# BLE-BMS.net
KiCad netlist of a schematic drawn in EAGLE
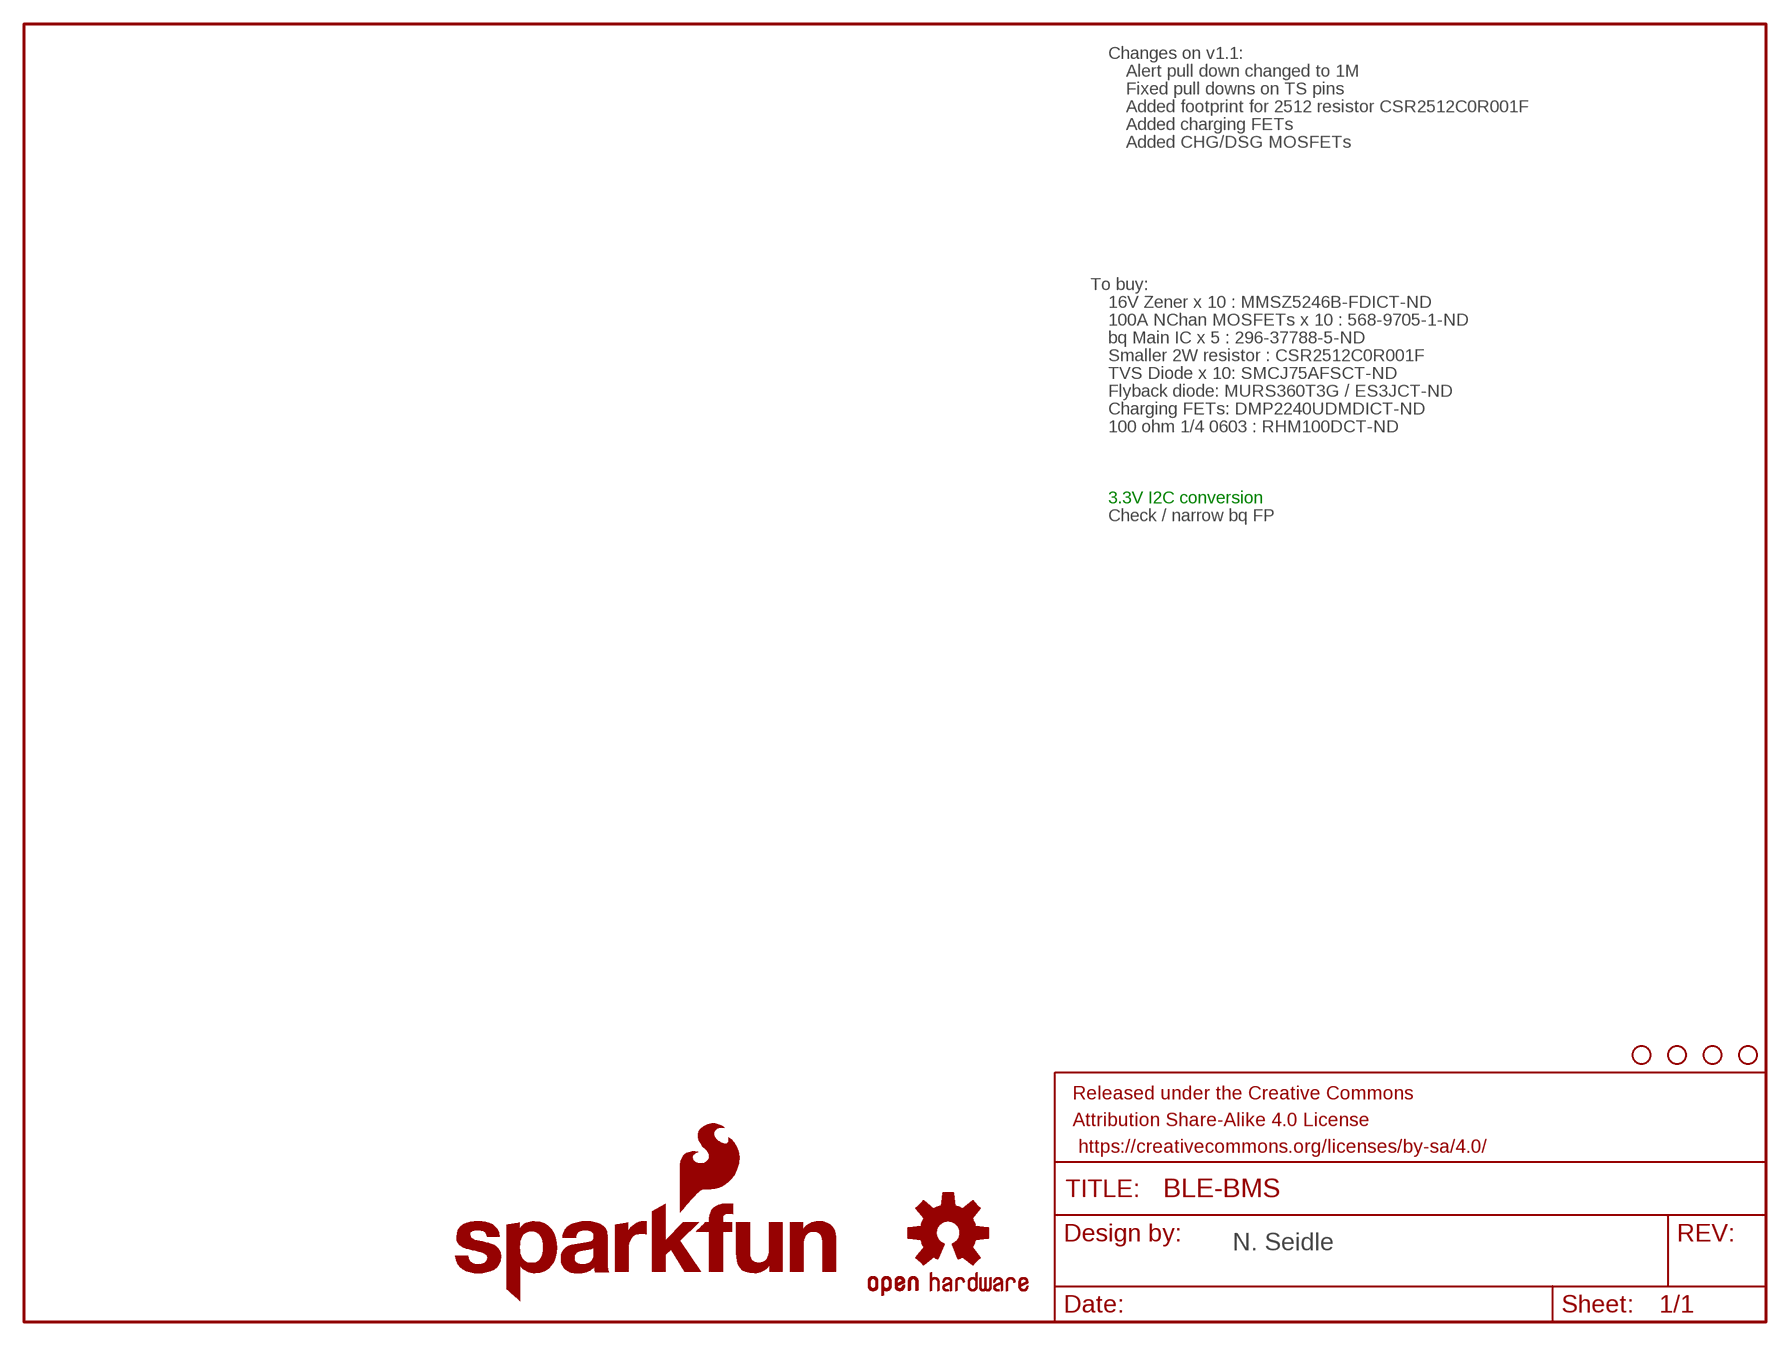
[diagram p0: schematic, sheet 1, part 1 of 3]
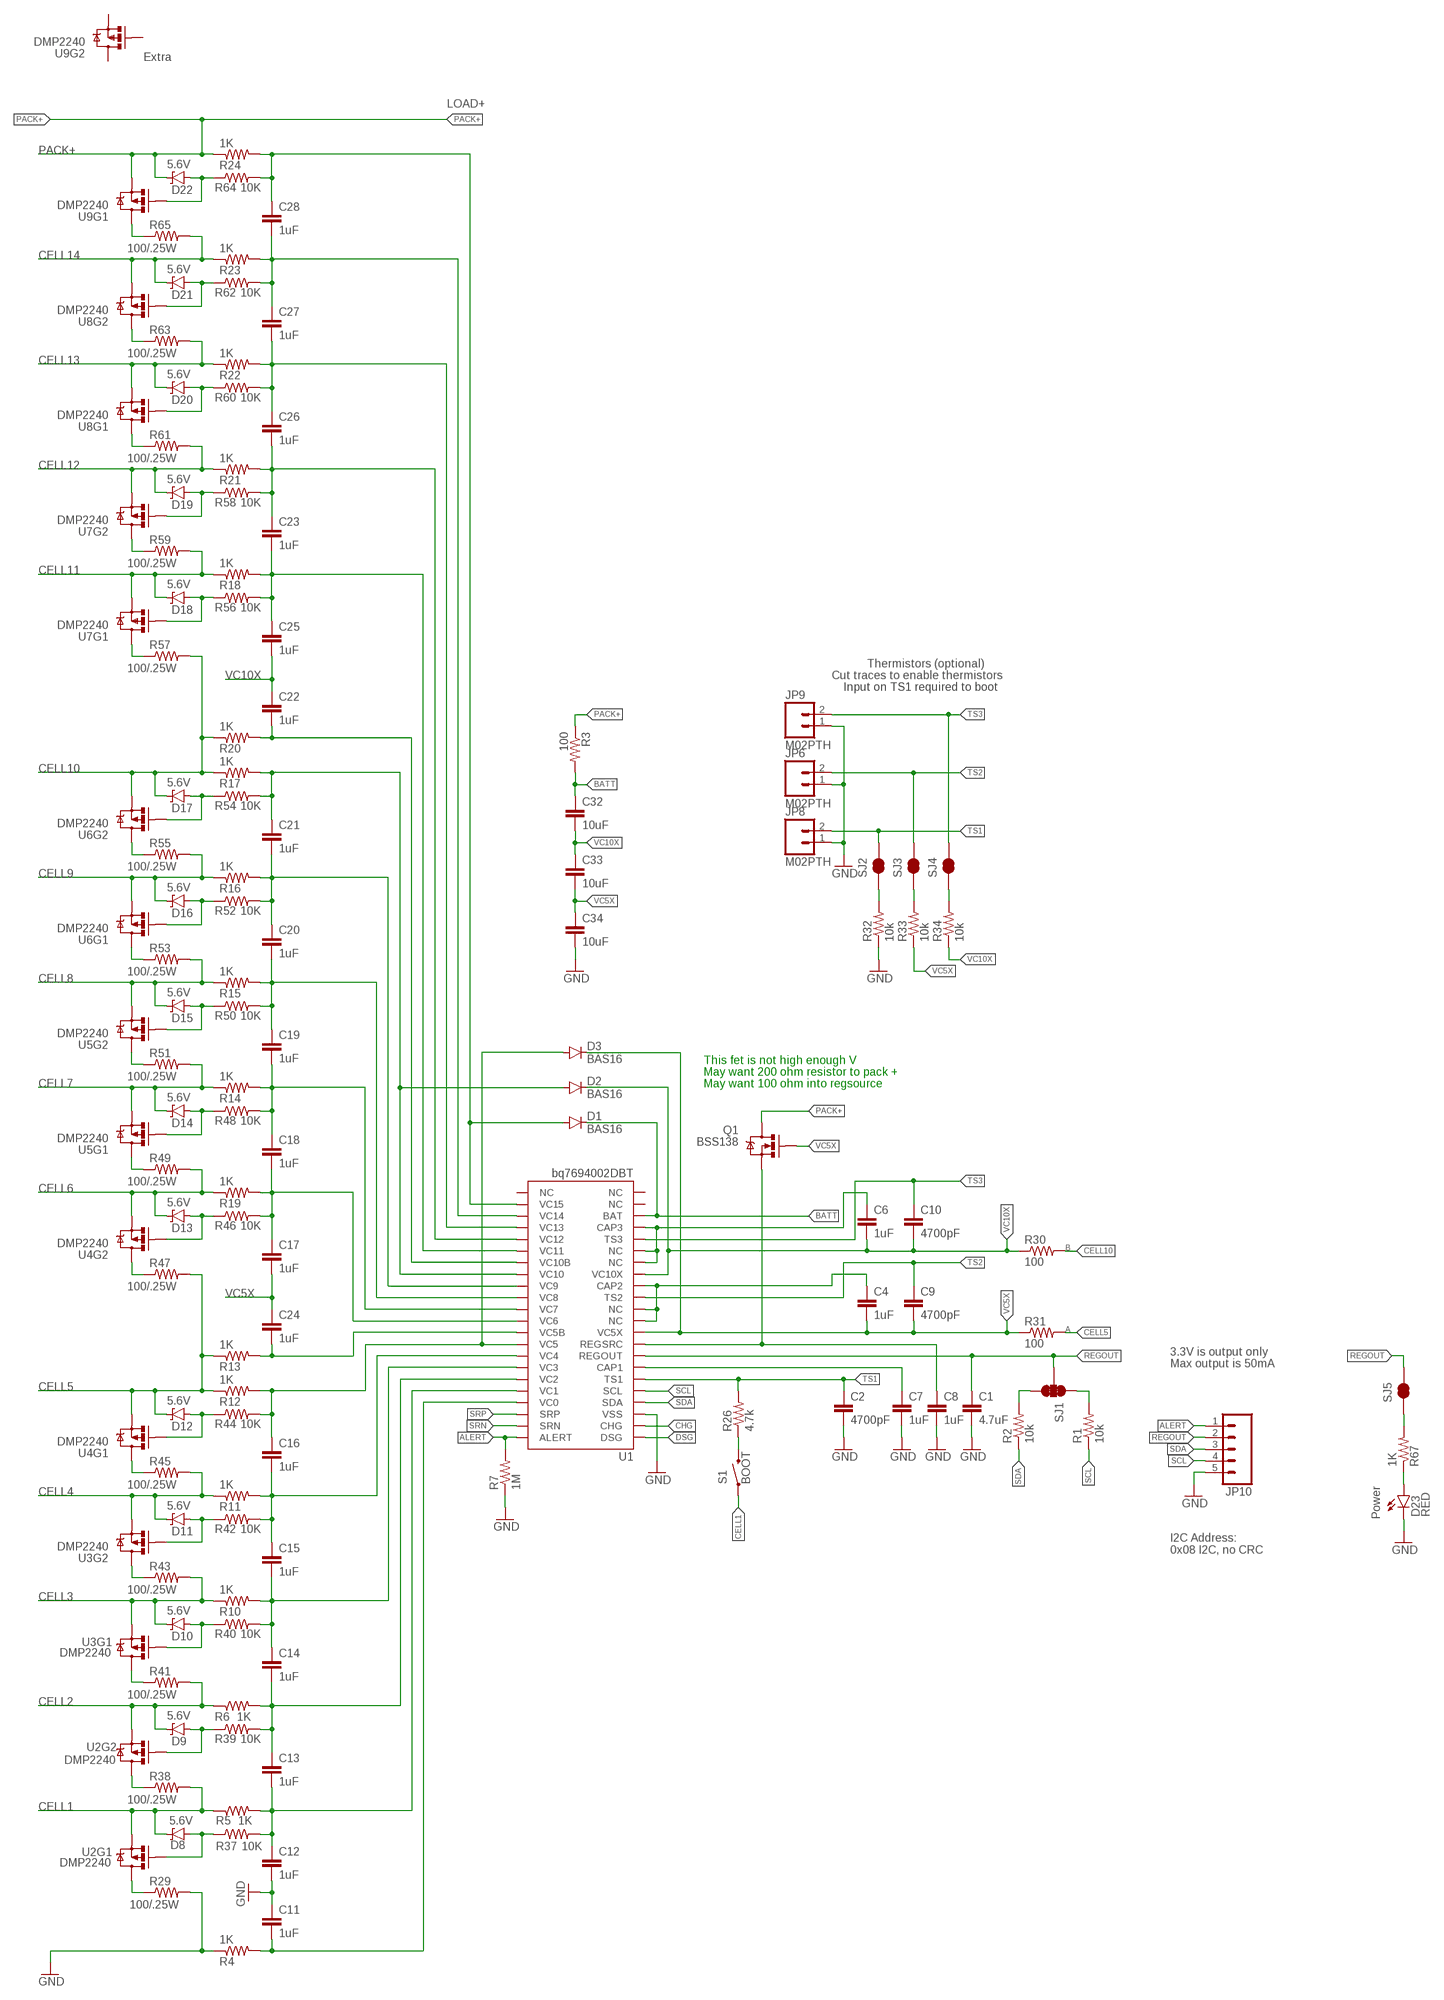
[diagram p1: schematic, sheet 1, part 2 of 3]
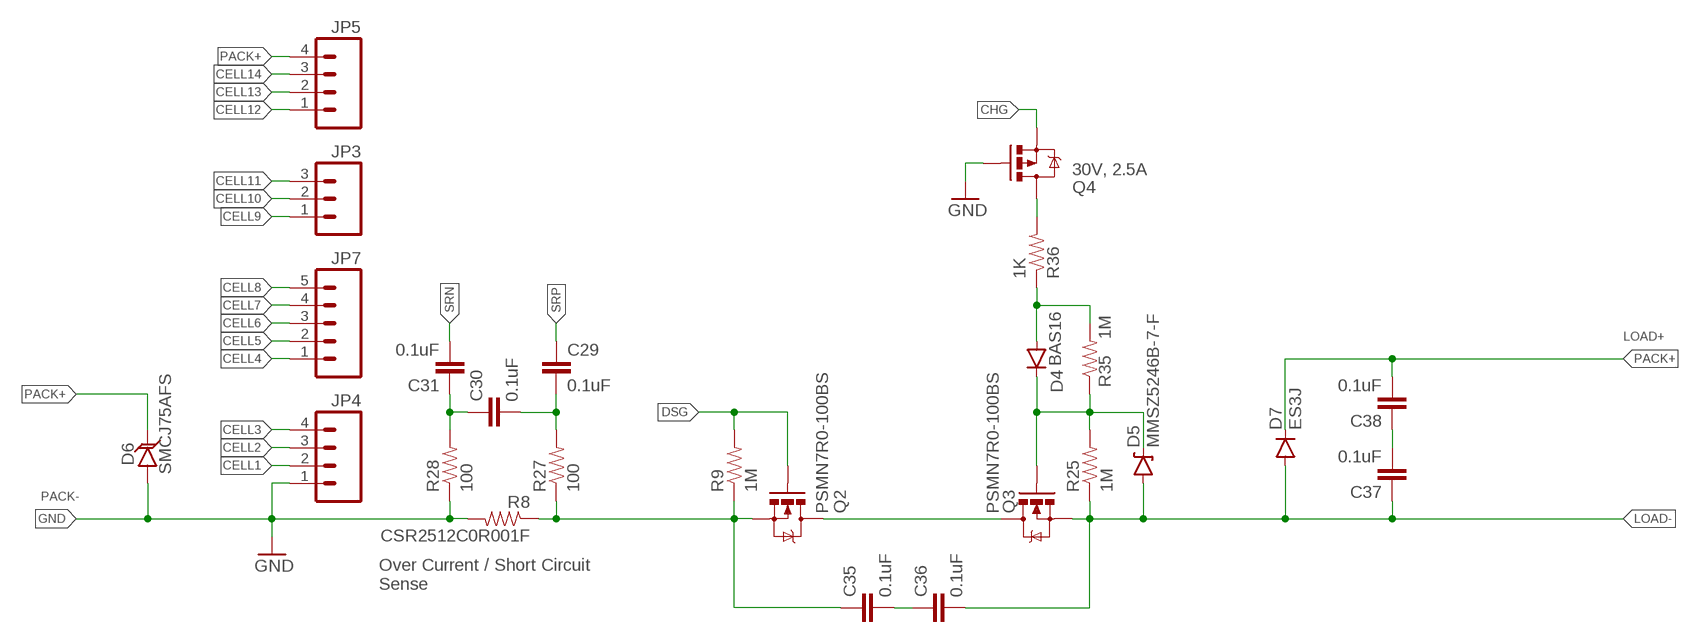
[diagram p2: schematic, sheet 1, part 3 of 3]

(export (version "E")
  (design (tool "Eeschema 10.0.6"))
  (components
    (comp (ref "C1")
      (value "4.7uF")
      (footprint "eagle-import:0603-CAP")
      (libsource (lib "eagle-import") (part "4.7UF-6.3V-10%(0603)0603"))
    )
    (comp (ref "C2")
      (value "4700pF")
      (footprint "eagle-import:0603-CAP")
      (libsource (lib "eagle-import") (part "4.7NF-50V-10%(0603)"))
    )
    (comp (ref "C4")
      (value "1uF")
      (footprint "eagle-import:0603-CAP")
      (libsource (lib "eagle-import") (part "1.0UF-16V-10%(0603)"))
    )
    (comp (ref "C6")
      (value "1uF")
      (footprint "eagle-import:0603-CAP")
      (libsource (lib "eagle-import") (part "1.0UF-16V-10%(0603)"))
    )
    (comp (ref "C7")
      (value "1uF")
      (footprint "eagle-import:0603-CAP")
      (libsource (lib "eagle-import") (part "1.0UF-16V-10%(0603)"))
    )
    (comp (ref "C8")
      (value "1uF")
      (footprint "eagle-import:0603-CAP")
      (libsource (lib "eagle-import") (part "1.0UF-16V-10%(0603)"))
    )
    (comp (ref "C9")
      (value "4700pF")
      (footprint "eagle-import:0603-CAP")
      (libsource (lib "eagle-import") (part "4.7NF-50V-10%(0603)"))
    )
    (comp (ref "C10")
      (value "4700pF")
      (footprint "eagle-import:0603-CAP")
      (libsource (lib "eagle-import") (part "4.7NF-50V-10%(0603)"))
    )
    (comp (ref "C11")
      (value "1uF")
      (footprint "eagle-import:0603-CAP")
      (libsource (lib "eagle-import") (part "1.0UF-16V-10%(0603)"))
    )
    (comp (ref "C12")
      (value "1uF")
      (footprint "eagle-import:0603-CAP")
      (libsource (lib "eagle-import") (part "1.0UF-16V-10%(0603)"))
    )
    (comp (ref "C13")
      (value "1uF")
      (footprint "eagle-import:0603-CAP")
      (libsource (lib "eagle-import") (part "1.0UF-16V-10%(0603)"))
    )
    (comp (ref "C14")
      (value "1uF")
      (footprint "eagle-import:0603-CAP")
      (libsource (lib "eagle-import") (part "1.0UF-16V-10%(0603)"))
    )
    (comp (ref "C15")
      (value "1uF")
      (footprint "eagle-import:0603-CAP")
      (libsource (lib "eagle-import") (part "1.0UF-16V-10%(0603)"))
    )
    (comp (ref "C16")
      (value "1uF")
      (footprint "eagle-import:0603-CAP")
      (libsource (lib "eagle-import") (part "1.0UF-16V-10%(0603)"))
    )
    (comp (ref "C17")
      (value "1uF")
      (footprint "eagle-import:0603-CAP")
      (libsource (lib "eagle-import") (part "1.0UF-16V-10%(0603)"))
    )
    (comp (ref "C18")
      (value "1uF")
      (footprint "eagle-import:0603-CAP")
      (libsource (lib "eagle-import") (part "1.0UF-16V-10%(0603)"))
    )
    (comp (ref "C19")
      (value "1uF")
      (footprint "eagle-import:0603-CAP")
      (libsource (lib "eagle-import") (part "1.0UF-16V-10%(0603)"))
    )
    (comp (ref "C20")
      (value "1uF")
      (footprint "eagle-import:0603-CAP")
      (libsource (lib "eagle-import") (part "1.0UF-16V-10%(0603)"))
    )
    (comp (ref "C21")
      (value "1uF")
      (footprint "eagle-import:0603-CAP")
      (libsource (lib "eagle-import") (part "1.0UF-16V-10%(0603)"))
    )
    (comp (ref "C22")
      (value "1uF")
      (footprint "eagle-import:0603-CAP")
      (libsource (lib "eagle-import") (part "1.0UF-16V-10%(0603)"))
    )
    (comp (ref "C23")
      (value "1uF")
      (footprint "eagle-import:0603-CAP")
      (libsource (lib "eagle-import") (part "1.0UF-16V-10%(0603)"))
    )
    (comp (ref "C24")
      (value "1uF")
      (footprint "eagle-import:0603-CAP")
      (libsource (lib "eagle-import") (part "1.0UF-16V-10%(0603)"))
    )
    (comp (ref "C25")
      (value "1uF")
      (footprint "eagle-import:0603-CAP")
      (libsource (lib "eagle-import") (part "1.0UF-16V-10%(0603)"))
    )
    (comp (ref "C26")
      (value "1uF")
      (footprint "eagle-import:0603-CAP")
      (libsource (lib "eagle-import") (part "1.0UF-16V-10%(0603)"))
    )
    (comp (ref "C27")
      (value "1uF")
      (footprint "eagle-import:0603-CAP")
      (libsource (lib "eagle-import") (part "1.0UF-16V-10%(0603)"))
    )
    (comp (ref "C28")
      (value "1uF")
      (footprint "eagle-import:0603-CAP")
      (libsource (lib "eagle-import") (part "1.0UF-16V-10%(0603)"))
    )
    (comp (ref "C29")
      (value "0.1uF")
      (footprint "eagle-import:0603-CAP")
      (libsource (lib "eagle-import") (part "0.1UF-25V(+80/-20%)(0603)"))
    )
    (comp (ref "C30")
      (value "0.1uF")
      (footprint "eagle-import:0603-CAP")
      (libsource (lib "eagle-import") (part "0.1UF-25V(+80/-20%)(0603)"))
    )
    (comp (ref "C31")
      (value "0.1uF")
      (footprint "eagle-import:0603-CAP")
      (libsource (lib "eagle-import") (part "0.1UF-25V(+80/-20%)(0603)"))
    )
    (comp (ref "C32")
      (value "10uF")
      (footprint "eagle-import:1210")
      (libsource (lib "eagle-import") (part "10UF50V20%(1210)"))
    )
    (comp (ref "C33")
      (value "10uF")
      (footprint "eagle-import:1210")
      (libsource (lib "eagle-import") (part "10UF50V20%(1210)"))
    )
    (comp (ref "C34")
      (value "10uF")
      (footprint "eagle-import:1210")
      (libsource (lib "eagle-import") (part "10UF50V20%(1210)"))
    )
    (comp (ref "C35")
      (value "0.1uF")
      (footprint "eagle-import:0603-CAP")
      (libsource (lib "eagle-import") (part "0.1UF-100V-10%(0603)"))
    )
    (comp (ref "C36")
      (value "0.1uF")
      (footprint "eagle-import:0603-CAP")
      (libsource (lib "eagle-import") (part "0.1UF-100V-10%(0603)"))
    )
    (comp (ref "C37")
      (value "0.1uF")
      (footprint "eagle-import:0603-CAP")
      (libsource (lib "eagle-import") (part "0.1UF-100V-10%(0603)"))
    )
    (comp (ref "C38")
      (value "0.1uF")
      (footprint "eagle-import:0603-CAP")
      (libsource (lib "eagle-import") (part "0.1UF-100V-10%(0603)"))
    )
    (comp (ref "D1")
      (value "BAS16")
      (footprint "eagle-import:SOD-323")
      (libsource (lib "eagle-import") (part "DIODESOD"))
    )
    (comp (ref "D2")
      (value "BAS16")
      (footprint "eagle-import:SOD-323")
      (libsource (lib "eagle-import") (part "DIODESOD"))
    )
    (comp (ref "D3")
      (value "BAS16")
      (footprint "eagle-import:SOD-323")
      (libsource (lib "eagle-import") (part "DIODESOD"))
    )
    (comp (ref "D4")
      (value "BAS16")
      (footprint "eagle-import:SOD-323")
      (libsource (lib "eagle-import") (part "DIODESOD"))
    )
    (comp (ref "D5")
      (value "MMSZ5246B-7-F")
      (footprint "eagle-import:SOD-123")
      (libsource (lib "eagle-import") (part "DIODE-ZENERSOD-123"))
    )
    (comp (ref "D6")
      (value "SMCJ75AFS")
      (footprint "eagle-import:SMC")
      (libsource (lib "eagle-import") (part "TVSSMC"))
    )
    (comp (ref "D7")
      (value "ES3J")
      (footprint "eagle-import:SMC")
      (libsource (lib "eagle-import") (part "DIODESMC/DO-214AB"))
    )
    (comp (ref "D8")
      (value "5.6V")
      (footprint "eagle-import:SOD-323")
      (libsource (lib "eagle-import") (part "DIODE-ZENER3.3V"))
    )
    (comp (ref "D9")
      (value "5.6V")
      (footprint "eagle-import:SOD-323")
      (libsource (lib "eagle-import") (part "DIODE-ZENER3.3V"))
    )
    (comp (ref "D10")
      (value "5.6V")
      (footprint "eagle-import:SOD-323")
      (libsource (lib "eagle-import") (part "DIODE-ZENER3.3V"))
    )
    (comp (ref "D11")
      (value "5.6V")
      (footprint "eagle-import:SOD-323")
      (libsource (lib "eagle-import") (part "DIODE-ZENER3.3V"))
    )
    (comp (ref "D12")
      (value "5.6V")
      (footprint "eagle-import:SOD-323")
      (libsource (lib "eagle-import") (part "DIODE-ZENER3.3V"))
    )
    (comp (ref "D13")
      (value "5.6V")
      (footprint "eagle-import:SOD-323")
      (libsource (lib "eagle-import") (part "DIODE-ZENER3.3V"))
    )
    (comp (ref "D14")
      (value "5.6V")
      (footprint "eagle-import:SOD-323")
      (libsource (lib "eagle-import") (part "DIODE-ZENER3.3V"))
    )
    (comp (ref "D15")
      (value "5.6V")
      (footprint "eagle-import:SOD-323")
      (libsource (lib "eagle-import") (part "DIODE-ZENER3.3V"))
    )
    (comp (ref "D16")
      (value "5.6V")
      (footprint "eagle-import:SOD-323")
      (libsource (lib "eagle-import") (part "DIODE-ZENER3.3V"))
    )
    (comp (ref "D17")
      (value "5.6V")
      (footprint "eagle-import:SOD-323")
      (libsource (lib "eagle-import") (part "DIODE-ZENER3.3V"))
    )
    (comp (ref "D18")
      (value "5.6V")
      (footprint "eagle-import:SOD-323")
      (libsource (lib "eagle-import") (part "DIODE-ZENER3.3V"))
    )
    (comp (ref "D19")
      (value "5.6V")
      (footprint "eagle-import:SOD-323")
      (libsource (lib "eagle-import") (part "DIODE-ZENER3.3V"))
    )
    (comp (ref "D20")
      (value "5.6V")
      (footprint "eagle-import:SOD-323")
      (libsource (lib "eagle-import") (part "DIODE-ZENER3.3V"))
    )
    (comp (ref "D21")
      (value "5.6V")
      (footprint "eagle-import:SOD-323")
      (libsource (lib "eagle-import") (part "DIODE-ZENER3.3V"))
    )
    (comp (ref "D22")
      (value "5.6V")
      (footprint "eagle-import:SOD-323")
      (libsource (lib "eagle-import") (part "DIODE-ZENER3.3V"))
    )
    (comp (ref "D23")
      (value "RED")
      (footprint "eagle-import:LED-1206")
      (libsource (lib "eagle-import") (part "LED-RED1206"))
    )
    (comp (ref "FRAME1")
      (value "FRAME-LETTER")
      (footprint "eagle-import:CREATIVE_COMMONS")
      (libsource (lib "eagle-import") (part "FRAME-LETTER"))
    )
    (comp (ref "JP3")
      (value "M03JST-PTH")
      (footprint "eagle-import:JST-3-PTH")
      (libsource (lib "eagle-import") (part "M03JST-PTH"))
    )
    (comp (ref "JP4")
      (value "M04JST-PTH")
      (footprint "eagle-import:JST-4-PTH")
      (libsource (lib "eagle-import") (part "M04JST-PTH"))
    )
    (comp (ref "JP5")
      (value "M04JST-PTH")
      (footprint "eagle-import:JST-4-PTH")
      (libsource (lib "eagle-import") (part "M04JST-PTH"))
    )
    (comp (ref "JP6")
      (value "M02PTH")
      (footprint "eagle-import:1X02")
      (libsource (lib "eagle-import") (part "M02PTH"))
    )
    (comp (ref "JP7")
      (value "M05JST")
      (footprint "eagle-import:JST-5-PTH")
      (libsource (lib "eagle-import") (part "M05JST"))
    )
    (comp (ref "JP8")
      (value "M02PTH")
      (footprint "eagle-import:1X02")
      (libsource (lib "eagle-import") (part "M02PTH"))
    )
    (comp (ref "JP9")
      (value "M02PTH")
      (footprint "eagle-import:1X02")
      (libsource (lib "eagle-import") (part "M02PTH"))
    )
    (comp (ref "JP10")
      (value "M05PTH")
      (footprint "eagle-import:1X05")
      (libsource (lib "eagle-import") (part "M05PTH"))
    )
    (comp (ref "LOGO1")
      (value "SFE_LOGO_NAME_FLAME.1_INCH")
      (footprint "eagle-import:SFE_LOGO_NAME_FLAME_.1")
      (libsource (lib "eagle-import") (part "SFE_LOGO_NAME_FLAME.1_INCH"))
    )
    (comp (ref "Q1")
      (value "BSS138")
      (footprint "eagle-import:SOT23-3")
      (libsource (lib "eagle-import") (part "MOSFET-NCHANNELBSS138"))
    )
    (comp (ref "Q2")
      (value "PSMN7R0-100BS")
      (footprint "eagle-import:TO-263_D2PAK")
      (libsource (lib "eagle-import") (part "MOSFET-NCHANNELPSMN7R0"))
    )
    (comp (ref "Q3")
      (value "PSMN7R0-100BS")
      (footprint "eagle-import:TO-263_D2PAK")
      (libsource (lib "eagle-import") (part "MOSFET-NCHANNELPSMN7R0"))
    )
    (comp (ref "Q4")
      (value "30V, 2.5A")
      (footprint "eagle-import:SOT23-3")
      (libsource (lib "eagle-import") (part "MOSFET-PCHANNELDMG2307L"))
    )
    (comp (ref "R1")
      (value "10k")
      (footprint "eagle-import:0603-RES")
      (libsource (lib "eagle-import") (part "10KOHM1/10W1%(0603)0603"))
    )
    (comp (ref "R2")
      (value "10k")
      (footprint "eagle-import:0603-RES")
      (libsource (lib "eagle-import") (part "10KOHM1/10W1%(0603)0603"))
    )
    (comp (ref "R3")
      (value "100")
      (footprint "eagle-import:0603-RES")
      (libsource (lib "eagle-import") (part "100OHM1/10W1%(0603)"))
    )
    (comp (ref "R4")
      (value "1K")
      (footprint "eagle-import:0603-RES")
      (libsource (lib "eagle-import") (part "1KOHM1/10W1%(0603)"))
    )
    (comp (ref "R5")
      (value "1K")
      (footprint "eagle-import:0603-RES")
      (libsource (lib "eagle-import") (part "1KOHM1/10W1%(0603)"))
    )
    (comp (ref "R6")
      (value "1K")
      (footprint "eagle-import:0603-RES")
      (libsource (lib "eagle-import") (part "1KOHM1/10W1%(0603)"))
    )
    (comp (ref "R7")
      (value "1M")
      (footprint "eagle-import:0603-RES")
      (libsource (lib "eagle-import") (part "1MOHM1/10W1%(0603)"))
    )
    (comp (ref "R8")
      (value "CSR2512C0R001F")
      (footprint "eagle-import:2512")
      (libsource (lib "eagle-import") (part "RESISTOR2512"))
    )
    (comp (ref "R9")
      (value "1M")
      (footprint "eagle-import:0603-RES")
      (libsource (lib "eagle-import") (part "1MOHM1/10W1%(0603)"))
    )
    (comp (ref "R10")
      (value "1K")
      (footprint "eagle-import:0603-RES")
      (libsource (lib "eagle-import") (part "1KOHM1/10W1%(0603)"))
    )
    (comp (ref "R11")
      (value "1K")
      (footprint "eagle-import:0603-RES")
      (libsource (lib "eagle-import") (part "1KOHM1/10W1%(0603)"))
    )
    (comp (ref "R12")
      (value "1K")
      (footprint "eagle-import:0603-RES")
      (libsource (lib "eagle-import") (part "1KOHM1/10W1%(0603)"))
    )
    (comp (ref "R13")
      (value "1K")
      (footprint "eagle-import:0603-RES")
      (libsource (lib "eagle-import") (part "1KOHM1/10W1%(0603)"))
    )
    (comp (ref "R14")
      (value "1K")
      (footprint "eagle-import:0603-RES")
      (libsource (lib "eagle-import") (part "1KOHM1/10W1%(0603)"))
    )
    (comp (ref "R15")
      (value "1K")
      (footprint "eagle-import:0603-RES")
      (libsource (lib "eagle-import") (part "1KOHM1/10W1%(0603)"))
    )
    (comp (ref "R16")
      (value "1K")
      (footprint "eagle-import:0603-RES")
      (libsource (lib "eagle-import") (part "1KOHM1/10W1%(0603)"))
    )
    (comp (ref "R17")
      (value "1K")
      (footprint "eagle-import:0603-RES")
      (libsource (lib "eagle-import") (part "1KOHM1/10W1%(0603)"))
    )
    (comp (ref "R18")
      (value "1K")
      (footprint "eagle-import:0603-RES")
      (libsource (lib "eagle-import") (part "1KOHM1/10W1%(0603)"))
    )
    (comp (ref "R19")
      (value "1K")
      (footprint "eagle-import:0603-RES")
      (libsource (lib "eagle-import") (part "1KOHM1/10W1%(0603)"))
    )
    (comp (ref "R20")
      (value "1K")
      (footprint "eagle-import:0603-RES")
      (libsource (lib "eagle-import") (part "1KOHM1/10W1%(0603)"))
    )
    (comp (ref "R21")
      (value "1K")
      (footprint "eagle-import:0603-RES")
      (libsource (lib "eagle-import") (part "1KOHM1/10W1%(0603)"))
    )
    (comp (ref "R22")
      (value "1K")
      (footprint "eagle-import:0603-RES")
      (libsource (lib "eagle-import") (part "1KOHM1/10W1%(0603)"))
    )
    (comp (ref "R23")
      (value "1K")
      (footprint "eagle-import:0603-RES")
      (libsource (lib "eagle-import") (part "1KOHM1/10W1%(0603)"))
    )
    (comp (ref "R24")
      (value "1K")
      (footprint "eagle-import:0603-RES")
      (libsource (lib "eagle-import") (part "1KOHM1/10W1%(0603)"))
    )
    (comp (ref "R25")
      (value "1M")
      (footprint "eagle-import:0603-RES")
      (libsource (lib "eagle-import") (part "1MOHM1/10W1%(0603)"))
    )
    (comp (ref "R26")
      (value "4.7k")
      (footprint "eagle-import:0603-RES")
      (libsource (lib "eagle-import") (part "4.7KOHM1/10W1%(0603)"))
    )
    (comp (ref "R27")
      (value "100")
      (footprint "eagle-import:0603-RES")
      (libsource (lib "eagle-import") (part "100OHM1/10W1%(0603)"))
    )
    (comp (ref "R28")
      (value "100")
      (footprint "eagle-import:0603-RES")
      (libsource (lib "eagle-import") (part "100OHM1/10W1%(0603)"))
    )
    (comp (ref "R29")
      (value "100/.25W")
      (footprint "eagle-import:0603-RES")
      (libsource (lib "eagle-import") (part "100OHM1/10W1%(0603)"))
    )
    (comp (ref "R30")
      (value "100")
      (footprint "eagle-import:0603-RES")
      (libsource (lib "eagle-import") (part "100OHM1/10W1%(0603)"))
    )
    (comp (ref "R31")
      (value "100")
      (footprint "eagle-import:0603-RES")
      (libsource (lib "eagle-import") (part "100OHM1/10W1%(0603)"))
    )
    (comp (ref "R32")
      (value "10k")
      (footprint "eagle-import:0603-RES")
      (libsource (lib "eagle-import") (part "10KOHM1/10W1%(0603)0603"))
    )
    (comp (ref "R33")
      (value "10k")
      (footprint "eagle-import:0603-RES")
      (libsource (lib "eagle-import") (part "10KOHM1/10W1%(0603)0603"))
    )
    (comp (ref "R34")
      (value "10k")
      (footprint "eagle-import:0603-RES")
      (libsource (lib "eagle-import") (part "10KOHM1/10W1%(0603)0603"))
    )
    (comp (ref "R35")
      (value "1M")
      (footprint "eagle-import:0603-RES")
      (libsource (lib "eagle-import") (part "1MOHM1/10W1%(0603)"))
    )
    (comp (ref "R36")
      (value "1K")
      (footprint "eagle-import:0603-RES")
      (libsource (lib "eagle-import") (part "1KOHM1/10W1%(0603)"))
    )
    (comp (ref "R37")
      (value "10K")
      (footprint "eagle-import:0603-RES")
      (libsource (lib "eagle-import") (part "10KOHM1/10W1%(0603)0603"))
    )
    (comp (ref "R38")
      (value "100/.25W")
      (footprint "eagle-import:0603-RES")
      (libsource (lib "eagle-import") (part "100OHM1/10W1%(0603)"))
    )
    (comp (ref "R39")
      (value "10K")
      (footprint "eagle-import:0603-RES")
      (libsource (lib "eagle-import") (part "10KOHM1/10W1%(0603)0603"))
    )
    (comp (ref "R40")
      (value "10K")
      (footprint "eagle-import:0603-RES")
      (libsource (lib "eagle-import") (part "10KOHM1/10W1%(0603)0603"))
    )
    (comp (ref "R41")
      (value "100/.25W")
      (footprint "eagle-import:0603-RES")
      (libsource (lib "eagle-import") (part "100OHM1/10W1%(0603)"))
    )
    (comp (ref "R42")
      (value "10K")
      (footprint "eagle-import:0603-RES")
      (libsource (lib "eagle-import") (part "10KOHM1/10W1%(0603)0603"))
    )
    (comp (ref "R43")
      (value "100/.25W")
      (footprint "eagle-import:0603-RES")
      (libsource (lib "eagle-import") (part "100OHM1/10W1%(0603)"))
    )
    (comp (ref "R44")
      (value "10K")
      (footprint "eagle-import:0603-RES")
      (libsource (lib "eagle-import") (part "10KOHM1/10W1%(0603)0603"))
    )
    (comp (ref "R45")
      (value "100/.25W")
      (footprint "eagle-import:0603-RES")
      (libsource (lib "eagle-import") (part "100OHM1/10W1%(0603)"))
    )
    (comp (ref "R46")
      (value "10K")
      (footprint "eagle-import:0603-RES")
      (libsource (lib "eagle-import") (part "10KOHM1/10W1%(0603)0603"))
    )
    (comp (ref "R47")
      (value "100/.25W")
      (footprint "eagle-import:0603-RES")
      (libsource (lib "eagle-import") (part "100OHM1/10W1%(0603)"))
    )
    (comp (ref "R48")
      (value "10K")
      (footprint "eagle-import:0603-RES")
      (libsource (lib "eagle-import") (part "10KOHM1/10W1%(0603)0603"))
    )
    (comp (ref "R49")
      (value "100/.25W")
      (footprint "eagle-import:0603-RES")
      (libsource (lib "eagle-import") (part "100OHM1/10W1%(0603)"))
    )
    (comp (ref "R50")
      (value "10K")
      (footprint "eagle-import:0603-RES")
      (libsource (lib "eagle-import") (part "10KOHM1/10W1%(0603)0603"))
    )
    (comp (ref "R51")
      (value "100/.25W")
      (footprint "eagle-import:0603-RES")
      (libsource (lib "eagle-import") (part "100OHM1/10W1%(0603)"))
    )
    (comp (ref "R52")
      (value "10K")
      (footprint "eagle-import:0603-RES")
      (libsource (lib "eagle-import") (part "10KOHM1/10W1%(0603)0603"))
    )
    (comp (ref "R53")
      (value "100/.25W")
      (footprint "eagle-import:0603-RES")
      (libsource (lib "eagle-import") (part "100OHM1/10W1%(0603)"))
    )
    (comp (ref "R54")
      (value "10K")
      (footprint "eagle-import:0603-RES")
      (libsource (lib "eagle-import") (part "10KOHM1/10W1%(0603)0603"))
    )
    (comp (ref "R55")
      (value "100/.25W")
      (footprint "eagle-import:0603-RES")
      (libsource (lib "eagle-import") (part "100OHM1/10W1%(0603)"))
    )
    (comp (ref "R56")
      (value "10K")
      (footprint "eagle-import:0603-RES")
      (libsource (lib "eagle-import") (part "10KOHM1/10W1%(0603)0603"))
    )
    (comp (ref "R57")
      (value "100/.25W")
      (footprint "eagle-import:0603-RES")
      (libsource (lib "eagle-import") (part "100OHM1/10W1%(0603)"))
    )
    (comp (ref "R58")
      (value "10K")
      (footprint "eagle-import:0603-RES")
      (libsource (lib "eagle-import") (part "10KOHM1/10W1%(0603)0603"))
    )
    (comp (ref "R59")
      (value "100/.25W")
      (footprint "eagle-import:0603-RES")
      (libsource (lib "eagle-import") (part "100OHM1/10W1%(0603)"))
    )
    (comp (ref "R60")
      (value "10K")
      (footprint "eagle-import:0603-RES")
      (libsource (lib "eagle-import") (part "10KOHM1/10W1%(0603)0603"))
    )
    (comp (ref "R61")
      (value "100/.25W")
      (footprint "eagle-import:0603-RES")
      (libsource (lib "eagle-import") (part "100OHM1/10W1%(0603)"))
    )
    (comp (ref "R62")
      (value "10K")
      (footprint "eagle-import:0603-RES")
      (libsource (lib "eagle-import") (part "10KOHM1/10W1%(0603)0603"))
    )
    (comp (ref "R63")
      (value "100/.25W")
      (footprint "eagle-import:0603-RES")
      (libsource (lib "eagle-import") (part "100OHM1/10W1%(0603)"))
    )
    (comp (ref "R64")
      (value "10K")
      (footprint "eagle-import:0603-RES")
      (libsource (lib "eagle-import") (part "10KOHM1/10W1%(0603)0603"))
    )
    (comp (ref "R65")
      (value "100/.25W")
      (footprint "eagle-import:0603-RES")
      (libsource (lib "eagle-import") (part "100OHM1/10W1%(0603)"))
    )
    (comp (ref "R67")
      (value "1K")
      (footprint "eagle-import:0603-RES")
      (libsource (lib "eagle-import") (part "1KOHM1/10W1%(0603)"))
    )
    (comp (ref "S1")
      (value "BOOT")
      (footprint "eagle-import:TACTILE-SWITCH-1101NE")
      (libsource (lib "eagle-import") (part "SWITCH-MOMENTARY-2-SMD-1101NE"))
    )
    (comp (ref "SJ1")
      (value "JUMPER-PAD-3-NC_BY_TRACE")
      (footprint "eagle-import:PAD-JUMPER-3-3OF3_NC_BY_TRACE_YES_SILK_FULL_BOX")
      (libsource (lib "eagle-import") (part "JUMPER-PAD-3-NC_BY_TRACE"))
    )
    (comp (ref "SJ2")
      (value "JUMPER-PAD-2-NC_BY_TRACE")
      (footprint "eagle-import:PAD-JUMPER-2-NC_BY_TRACE_YES_SILK")
      (libsource (lib "eagle-import") (part "JUMPER-PAD-2-NC_BY_TRACE"))
    )
    (comp (ref "SJ3")
      (value "JUMPER-PAD-2-NC_BY_TRACE")
      (footprint "eagle-import:PAD-JUMPER-2-NC_BY_TRACE_YES_SILK")
      (libsource (lib "eagle-import") (part "JUMPER-PAD-2-NC_BY_TRACE"))
    )
    (comp (ref "SJ4")
      (value "JUMPER-PAD-2-NC_BY_TRACE")
      (footprint "eagle-import:PAD-JUMPER-2-NC_BY_TRACE_YES_SILK")
      (libsource (lib "eagle-import") (part "JUMPER-PAD-2-NC_BY_TRACE"))
    )
    (comp (ref "SJ5")
      (value "JUMPER-PAD-2-NC_BY_TRACE")
      (footprint "eagle-import:PAD-JUMPER-2-NC_BY_TRACE_YES_SILK")
      (libsource (lib "eagle-import") (part "JUMPER-PAD-2-NC_BY_TRACE"))
    )
    (comp (ref "STANDOFF1")
      (value "STAND-OFF")
      (footprint "eagle-import:STAND-OFF")
      (libsource (lib "eagle-import") (part "STAND-OFF"))
    )
    (comp (ref "STANDOFF2")
      (value "STAND-OFF")
      (footprint "eagle-import:STAND-OFF")
      (libsource (lib "eagle-import") (part "STAND-OFF"))
    )
    (comp (ref "STANDOFF3")
      (value "STAND-OFF")
      (footprint "eagle-import:STAND-OFF")
      (libsource (lib "eagle-import") (part "STAND-OFF"))
    )
    (comp (ref "STANDOFF4")
      (value "STAND-OFF")
      (footprint "eagle-import:STAND-OFF")
      (libsource (lib "eagle-import") (part "STAND-OFF"))
    )
    (comp (ref "U$7")
      (value "OSHW-LOGOS")
      (footprint "eagle-import:OSHW-LOGO-S")
      (libsource (lib "eagle-import") (part "OSHW-LOGOS"))
    )
    (comp (ref "U1")
      (value "bq7694002DBT")
      (footprint "eagle-import:44-TSSOP")
      (libsource (lib "eagle-import") (part "BQ7694040"))
    )
    (comp (ref "U2")
      (value "DMP2240")
      (footprint "eagle-import:SOT26")
      (libsource (lib "eagle-import") (part "MOSFET-PCHANNEL_DUALSOT26"))
    )
    (comp (ref "U3")
      (value "DMP2240")
      (footprint "eagle-import:SOT26")
      (libsource (lib "eagle-import") (part "MOSFET-PCHANNEL_DUALSOT26"))
    )
    (comp (ref "U4")
      (value "DMP2240")
      (footprint "eagle-import:SOT26")
      (libsource (lib "eagle-import") (part "MOSFET-PCHANNEL_DUALSOT26"))
    )
    (comp (ref "U5")
      (value "DMP2240")
      (footprint "eagle-import:SOT26")
      (libsource (lib "eagle-import") (part "MOSFET-PCHANNEL_DUALSOT26"))
    )
    (comp (ref "U6")
      (value "DMP2240")
      (footprint "eagle-import:SOT26")
      (libsource (lib "eagle-import") (part "MOSFET-PCHANNEL_DUALSOT26"))
    )
    (comp (ref "U7")
      (value "DMP2240")
      (footprint "eagle-import:SOT26")
      (libsource (lib "eagle-import") (part "MOSFET-PCHANNEL_DUALSOT26"))
    )
    (comp (ref "U8")
      (value "DMP2240")
      (footprint "eagle-import:SOT26")
      (libsource (lib "eagle-import") (part "MOSFET-PCHANNEL_DUALSOT26"))
    )
    (comp (ref "U9")
      (value "DMP2240")
      (footprint "eagle-import:SOT26")
      (libsource (lib "eagle-import") (part "MOSFET-PCHANNEL_DUALSOT26"))
    )
  )
  (nets
    (net (code "1") (name "ALERT") (class "Default")
      (node (ref "JP10") (pin "1") (pinfunction "1_1") (pintype "passive"))
      (node (ref "R7") (pin "2") (pinfunction "2_2") (pintype "passive"))
      (node (ref "U1") (pin "44") (pinfunction "ALERT_44") (pintype "bidirectional"))
    )
    (net (code "2") (name "BATT") (class "Default")
      (node (ref "C32") (pin "1") (pinfunction "1_1") (pintype "passive"))
      (node (ref "D1") (pin "C") (pinfunction "C_C") (pintype "passive"))
      (node (ref "R3") (pin "2") (pinfunction "2_2") (pintype "passive"))
      (node (ref "U1") (pin "20") (pinfunction "BAT_20") (pintype "bidirectional"))
    )
    (net (code "3") (name "CELL1") (class "Default")
      (node (ref "D8") (pin "C") (pinfunction "C_C") (pintype "passive"))
      (node (ref "JP4") (pin "2") (pinfunction "2_2") (pintype "passive"))
      (node (ref "R38") (pin "2") (pinfunction "2_2") (pintype "passive"))
      (node (ref "R5") (pin "1") (pinfunction "1_1") (pintype "passive"))
      (node (ref "S1") (pin "1") (pinfunction "1_1") (pintype "passive"))
      (node (ref "U2") (pin "S1") (pinfunction "S_S1") (pintype "passive"))
    )
    (net (code "4") (name "CELL2") (class "Default")
      (node (ref "D9") (pin "C") (pinfunction "C_C") (pintype "passive"))
      (node (ref "JP4") (pin "3") (pinfunction "3_3") (pintype "passive"))
      (node (ref "R41") (pin "2") (pinfunction "2_2") (pintype "passive"))
      (node (ref "R6") (pin "1") (pinfunction "1_1") (pintype "passive"))
      (node (ref "U2") (pin "S2") (pinfunction "S_S2") (pintype "passive"))
    )
    (net (code "5") (name "CELL3") (class "Default")
      (node (ref "D10") (pin "C") (pinfunction "C_C") (pintype "passive"))
      (node (ref "JP4") (pin "4") (pinfunction "4_4") (pintype "passive"))
      (node (ref "R10") (pin "1") (pinfunction "1_1") (pintype "passive"))
      (node (ref "R43") (pin "2") (pinfunction "2_2") (pintype "passive"))
      (node (ref "U3") (pin "S1") (pinfunction "S_S1") (pintype "passive"))
    )
    (net (code "6") (name "CELL4") (class "Default")
      (node (ref "D11") (pin "C") (pinfunction "C_C") (pintype "passive"))
      (node (ref "JP7") (pin "1") (pinfunction "1_1") (pintype "passive"))
      (node (ref "R11") (pin "1") (pinfunction "1_1") (pintype "passive"))
      (node (ref "R45") (pin "2") (pinfunction "2_2") (pintype "passive"))
      (node (ref "U3") (pin "S2") (pinfunction "S_S2") (pintype "passive"))
    )
    (net (code "7") (name "CELL5") (class "Default")
      (node (ref "D12") (pin "C") (pinfunction "C_C") (pintype "passive"))
      (node (ref "JP7") (pin "2") (pinfunction "2_2") (pintype "passive"))
      (node (ref "R12") (pin "1") (pinfunction "1_1") (pintype "passive"))
      (node (ref "R13") (pin "1") (pinfunction "1_1") (pintype "passive"))
      (node (ref "R31") (pin "2") (pinfunction "2_2") (pintype "passive"))
      (node (ref "R47") (pin "2") (pinfunction "2_2") (pintype "passive"))
      (node (ref "U4") (pin "S1") (pinfunction "S_S1") (pintype "passive"))
    )
    (net (code "8") (name "CELL6") (class "Default")
      (node (ref "D13") (pin "C") (pinfunction "C_C") (pintype "passive"))
      (node (ref "JP7") (pin "3") (pinfunction "3_3") (pintype "passive"))
      (node (ref "R19") (pin "1") (pinfunction "1_1") (pintype "passive"))
      (node (ref "R49") (pin "2") (pinfunction "2_2") (pintype "passive"))
      (node (ref "U4") (pin "S2") (pinfunction "S_S2") (pintype "passive"))
    )
    (net (code "9") (name "CELL7") (class "Default")
      (node (ref "D14") (pin "C") (pinfunction "C_C") (pintype "passive"))
      (node (ref "JP7") (pin "4") (pinfunction "4_4") (pintype "passive"))
      (node (ref "R14") (pin "1") (pinfunction "1_1") (pintype "passive"))
      (node (ref "R51") (pin "2") (pinfunction "2_2") (pintype "passive"))
      (node (ref "U5") (pin "S1") (pinfunction "S_S1") (pintype "passive"))
    )
    (net (code "10") (name "CELL8") (class "Default")
      (node (ref "D15") (pin "C") (pinfunction "C_C") (pintype "passive"))
      (node (ref "JP7") (pin "5") (pinfunction "5_5") (pintype "passive"))
      (node (ref "R15") (pin "1") (pinfunction "1_1") (pintype "passive"))
      (node (ref "R53") (pin "2") (pinfunction "2_2") (pintype "passive"))
      (node (ref "U5") (pin "S2") (pinfunction "S_S2") (pintype "passive"))
    )
    (net (code "11") (name "CELL9") (class "Default")
      (node (ref "D16") (pin "C") (pinfunction "C_C") (pintype "passive"))
      (node (ref "JP3") (pin "1") (pinfunction "1_1") (pintype "passive"))
      (node (ref "R16") (pin "1") (pinfunction "1_1") (pintype "passive"))
      (node (ref "R55") (pin "2") (pinfunction "2_2") (pintype "passive"))
      (node (ref "U6") (pin "S1") (pinfunction "S_S1") (pintype "passive"))
    )
    (net (code "12") (name "CELL10") (class "Default")
      (node (ref "D17") (pin "C") (pinfunction "C_C") (pintype "passive"))
      (node (ref "JP3") (pin "2") (pinfunction "2_2") (pintype "passive"))
      (node (ref "R17") (pin "1") (pinfunction "1_1") (pintype "passive"))
      (node (ref "R20") (pin "1") (pinfunction "1_1") (pintype "passive"))
      (node (ref "R30") (pin "2") (pinfunction "2_2") (pintype "passive"))
      (node (ref "R57") (pin "2") (pinfunction "2_2") (pintype "passive"))
      (node (ref "U6") (pin "S2") (pinfunction "S_S2") (pintype "passive"))
    )
    (net (code "13") (name "CELL11") (class "Default")
      (node (ref "D18") (pin "C") (pinfunction "C_C") (pintype "passive"))
      (node (ref "JP3") (pin "3") (pinfunction "3_3") (pintype "passive"))
      (node (ref "R18") (pin "1") (pinfunction "1_1") (pintype "passive"))
      (node (ref "R59") (pin "2") (pinfunction "2_2") (pintype "passive"))
      (node (ref "U7") (pin "S1") (pinfunction "S_S1") (pintype "passive"))
    )
    (net (code "14") (name "CELL12") (class "Default")
      (node (ref "D19") (pin "C") (pinfunction "C_C") (pintype "passive"))
      (node (ref "JP5") (pin "1") (pinfunction "1_1") (pintype "passive"))
      (node (ref "R21") (pin "1") (pinfunction "1_1") (pintype "passive"))
      (node (ref "R61") (pin "2") (pinfunction "2_2") (pintype "passive"))
      (node (ref "U7") (pin "S2") (pinfunction "S_S2") (pintype "passive"))
    )
    (net (code "15") (name "CELL13") (class "Default")
      (node (ref "D20") (pin "C") (pinfunction "C_C") (pintype "passive"))
      (node (ref "JP5") (pin "2") (pinfunction "2_2") (pintype "passive"))
      (node (ref "R22") (pin "1") (pinfunction "1_1") (pintype "passive"))
      (node (ref "R63") (pin "2") (pinfunction "2_2") (pintype "passive"))
      (node (ref "U8") (pin "S1") (pinfunction "S_S1") (pintype "passive"))
    )
    (net (code "16") (name "CELL14") (class "Default")
      (node (ref "D21") (pin "C") (pinfunction "C_C") (pintype "passive"))
      (node (ref "JP5") (pin "3") (pinfunction "3_3") (pintype "passive"))
      (node (ref "R23") (pin "1") (pinfunction "1_1") (pintype "passive"))
      (node (ref "R65") (pin "2") (pinfunction "2_2") (pintype "passive"))
      (node (ref "U8") (pin "S2") (pinfunction "S_S2") (pintype "passive"))
    )
    (net (code "17") (name "CHG") (class "Default")
      (node (ref "Q4") (pin "2") (pinfunction "S_2") (pintype "passive"))
      (node (ref "U1") (pin "2") (pinfunction "CHG_2") (pintype "bidirectional"))
    )
    (net (code "18") (name "DSG") (class "Default")
      (node (ref "Q2") (pin "1") (pinfunction "G_1") (pintype "passive"))
      (node (ref "R9") (pin "2") (pinfunction "2_2") (pintype "passive"))
      (node (ref "U1") (pin "1") (pinfunction "DSG_1") (pintype "bidirectional"))
    )
    (net (code "19") (name "GND") (class "Default")
      (node (ref "C1") (pin "2") (pinfunction "2_2") (pintype "passive"))
      (node (ref "C11") (pin "1") (pinfunction "1_1") (pintype "passive"))
      (node (ref "C12") (pin "2") (pinfunction "2_2") (pintype "passive"))
      (node (ref "C2") (pin "2") (pinfunction "2_2") (pintype "passive"))
      (node (ref "C34") (pin "2") (pinfunction "2_2") (pintype "passive"))
      (node (ref "C7") (pin "2") (pinfunction "2_2") (pintype "passive"))
      (node (ref "C8") (pin "2") (pinfunction "2_2") (pintype "passive"))
      (node (ref "D23") (pin "C") (pinfunction "C_C") (pintype "passive"))
      (node (ref "D6") (pin "A") (pinfunction "A_A") (pintype "passive"))
      (node (ref "JP10") (pin "5") (pinfunction "5_5") (pintype "passive"))
      (node (ref "JP4") (pin "1") (pinfunction "1_1") (pintype "passive"))
      (node (ref "JP6") (pin "1") (pinfunction "1_1") (pintype "passive"))
      (node (ref "JP8") (pin "1") (pinfunction "1_1") (pintype "passive"))
      (node (ref "JP9") (pin "1") (pinfunction "1_1") (pintype "passive"))
      (node (ref "Q4") (pin "1") (pinfunction "G_1") (pintype "passive"))
      (node (ref "R28") (pin "1") (pinfunction "1_1") (pintype "passive"))
      (node (ref "R29") (pin "2") (pinfunction "2_2") (pintype "passive"))
      (node (ref "R32") (pin "1") (pinfunction "1_1") (pintype "passive"))
      (node (ref "R4") (pin "1") (pinfunction "1_1") (pintype "passive"))
      (node (ref "R7") (pin "1") (pinfunction "1_1") (pintype "passive"))
      (node (ref "R8") (pin "2") (pinfunction "2_2") (pintype "passive"))
      (node (ref "U1") (pin "3") (pinfunction "VSS_3") (pintype "bidirectional"))
    )
    (net (code "20") (name "LOAD-") (class "Default")
      (node (ref "C36") (pin "2") (pinfunction "2_2") (pintype "passive"))
      (node (ref "C37") (pin "1") (pinfunction "1_1") (pintype "passive"))
      (node (ref "D5") (pin "A") (pinfunction "A_A") (pintype "passive"))
      (node (ref "D7") (pin "A") (pinfunction "A_A") (pintype "passive"))
      (node (ref "Q3") (pin "3") (pinfunction "S_3") (pintype "passive"))
      (node (ref "R25") (pin "1") (pinfunction "1_1") (pintype "passive"))
    )
    (net (code "21") (name "Net-(C29-Pad2)") (class "Default")
      (node (ref "C29") (pin "2") (pinfunction "2_2") (pintype "passive"))
      (node (ref "C30") (pin "2") (pinfunction "2_2") (pintype "passive"))
      (node (ref "R27") (pin "2") (pinfunction "2_2") (pintype "passive"))
    )
    (net (code "22") (name "Net-(C30-Pad1)") (class "Default")
      (node (ref "C30") (pin "1") (pinfunction "1_1") (pintype "passive"))
      (node (ref "C31") (pin "1") (pinfunction "1_1") (pintype "passive"))
      (node (ref "R28") (pin "2") (pinfunction "2_2") (pintype "passive"))
    )
    (net (code "23") (name "Net-(C35-Pad2)") (class "Default")
      (node (ref "C35") (pin "2") (pinfunction "2_2") (pintype "passive"))
      (node (ref "C36") (pin "1") (pinfunction "1_1") (pintype "passive"))
    )
    (net (code "24") (name "Net-(C37-Pad2)") (class "Default")
      (node (ref "C37") (pin "2") (pinfunction "2_2") (pintype "passive"))
      (node (ref "C38") (pin "1") (pinfunction "1_1") (pintype "passive"))
    )
    (net (code "25") (name "Net-(D4-PadA)") (class "Default")
      (node (ref "D4") (pin "A") (pinfunction "A_A") (pintype "passive"))
      (node (ref "R35") (pin "2") (pinfunction "2_2") (pintype "passive"))
      (node (ref "R36") (pin "1") (pinfunction "1_1") (pintype "passive"))
    )
    (net (code "26") (name "Net-(D23-PadA)") (class "Default")
      (node (ref "D23") (pin "A") (pinfunction "A_A") (pintype "passive"))
      (node (ref "R67") (pin "1") (pinfunction "1_1") (pintype "passive"))
    )
    (net (code "27") (name "Net-(Q1-S)") (class "Default")
      (node (ref "C8") (pin "1") (pinfunction "1_1") (pintype "passive"))
      (node (ref "Q1") (pin "2") (pinfunction "S_2") (pintype "passive"))
      (node (ref "U1") (pin "9") (pinfunction "REGSRC_9") (pintype "bidirectional"))
    )
    (net (code "28") (name "Net-(Q2-D)") (class "Default")
      (node (ref "Q2") (pin "2") (pinfunction "D_2") (pintype "passive"))
      (node (ref "Q3") (pin "2") (pinfunction "D_2") (pintype "passive"))
    )
    (net (code "29") (name "Net-(Q2-S)") (class "Default")
      (node (ref "C35") (pin "1") (pinfunction "1_1") (pintype "passive"))
      (node (ref "Q2") (pin "3") (pinfunction "S_3") (pintype "passive"))
      (node (ref "R27") (pin "1") (pinfunction "1_1") (pintype "passive"))
      (node (ref "R8") (pin "1") (pinfunction "1_1") (pintype "passive"))
      (node (ref "R9") (pin "1") (pinfunction "1_1") (pintype "passive"))
    )
    (net (code "30") (name "Net-(Q3-G)") (class "Default")
      (node (ref "D4") (pin "C") (pinfunction "C_C") (pintype "passive"))
      (node (ref "D5") (pin "C") (pinfunction "C_C") (pintype "passive"))
      (node (ref "Q3") (pin "1") (pinfunction "G_1") (pintype "passive"))
      (node (ref "R25") (pin "2") (pinfunction "2_2") (pintype "passive"))
      (node (ref "R35") (pin "1") (pinfunction "1_1") (pintype "passive"))
    )
    (net (code "31") (name "Net-(Q4-D)") (class "Default")
      (node (ref "Q4") (pin "3") (pinfunction "D_3") (pintype "passive"))
      (node (ref "R36") (pin "2") (pinfunction "2_2") (pintype "passive"))
    )
    (net (code "32") (name "Net-(R1-Pad2)") (class "Default")
      (node (ref "R1") (pin "2") (pinfunction "2_2") (pintype "passive"))
      (node (ref "SJ1") (pin "1") (pinfunction "1_1") (pintype "passive"))
    )
    (net (code "33") (name "Net-(R2-Pad2)") (class "Default")
      (node (ref "R2") (pin "2") (pinfunction "2_2") (pintype "passive"))
      (node (ref "SJ1") (pin "3") (pinfunction "3_3") (pintype "passive"))
    )
    (net (code "34") (name "Net-(R26-Pad1)") (class "Default")
      (node (ref "R26") (pin "1") (pinfunction "1_1") (pintype "passive"))
      (node (ref "S1") (pin "2") (pinfunction "2_2") (pintype "passive"))
    )
    (net (code "35") (name "Net-(R32-Pad2)") (class "Default")
      (node (ref "R32") (pin "2") (pinfunction "2_2") (pintype "passive"))
      (node (ref "SJ2") (pin "1") (pinfunction "1_1") (pintype "passive"))
    )
    (net (code "36") (name "Net-(R33-Pad2)") (class "Default")
      (node (ref "R33") (pin "2") (pinfunction "2_2") (pintype "passive"))
      (node (ref "SJ3") (pin "1") (pinfunction "1_1") (pintype "passive"))
    )
    (net (code "37") (name "Net-(R34-Pad2)") (class "Default")
      (node (ref "R34") (pin "2") (pinfunction "2_2") (pintype "passive"))
      (node (ref "SJ4") (pin "1") (pinfunction "1_1") (pintype "passive"))
    )
    (net (code "38") (name "Net-(R67-Pad2)") (class "Default")
      (node (ref "R67") (pin "2") (pinfunction "2_2") (pintype "passive"))
      (node (ref "SJ5") (pin "1") (pinfunction "1_1") (pintype "passive"))
    )
    (net (code "39") (name "Net-(U1-CAP1)") (class "Default")
      (node (ref "C7") (pin "1") (pinfunction "1_1") (pintype "passive"))
      (node (ref "U1") (pin "7") (pinfunction "CAP1_7") (pintype "bidirectional"))
    )
    (net (code "40") (name "Net-(U1-CAP2)") (class "Default")
      (node (ref "C4") (pin "1") (pinfunction "1_1") (pintype "passive"))
      (node (ref "U1") (pin "11") (pinfunction "NC_11") (pintype "bidirectional"))
      (node (ref "U1") (pin "12") (pinfunction "NC_12") (pintype "bidirectional"))
      (node (ref "U1") (pin "14") (pinfunction "CAP2_14") (pintype "bidirectional"))
    )
    (net (code "41") (name "Net-(U1-CAP3)") (class "Default")
      (node (ref "C6") (pin "1") (pinfunction "1_1") (pintype "passive"))
      (node (ref "U1") (pin "16") (pinfunction "NC_16") (pintype "bidirectional"))
      (node (ref "U1") (pin "17") (pinfunction "NC_17") (pintype "bidirectional"))
      (node (ref "U1") (pin "19") (pinfunction "CAP3_19") (pintype "bidirectional"))
    )
    (net (code "42") (name "Net-(U1-VC0)") (class "Default")
      (node (ref "C11") (pin "2") (pinfunction "2_2") (pintype "passive"))
      (node (ref "R4") (pin "2") (pinfunction "2_2") (pintype "passive"))
      (node (ref "U1") (pin "41") (pinfunction "VC0_41") (pintype "bidirectional"))
    )
    (net (code "43") (name "Net-(U1-VC1)") (class "Default")
      (node (ref "C12") (pin "1") (pinfunction "1_1") (pintype "passive"))
      (node (ref "C13") (pin "2") (pinfunction "2_2") (pintype "passive"))
      (node (ref "R37") (pin "2") (pinfunction "2_2") (pintype "passive"))
      (node (ref "R5") (pin "2") (pinfunction "2_2") (pintype "passive"))
      (node (ref "U1") (pin "40") (pinfunction "VC1_40") (pintype "bidirectional"))
    )
    (net (code "44") (name "Net-(U1-VC2)") (class "Default")
      (node (ref "C13") (pin "1") (pinfunction "1_1") (pintype "passive"))
      (node (ref "C14") (pin "2") (pinfunction "2_2") (pintype "passive"))
      (node (ref "R39") (pin "2") (pinfunction "2_2") (pintype "passive"))
      (node (ref "R6") (pin "2") (pinfunction "2_2") (pintype "passive"))
      (node (ref "U1") (pin "39") (pinfunction "VC2_39") (pintype "bidirectional"))
    )
    (net (code "45") (name "Net-(U1-VC3)") (class "Default")
      (node (ref "C14") (pin "1") (pinfunction "1_1") (pintype "passive"))
      (node (ref "C15") (pin "2") (pinfunction "2_2") (pintype "passive"))
      (node (ref "R10") (pin "2") (pinfunction "2_2") (pintype "passive"))
      (node (ref "R40") (pin "2") (pinfunction "2_2") (pintype "passive"))
      (node (ref "U1") (pin "38") (pinfunction "VC3_38") (pintype "bidirectional"))
    )
    (net (code "46") (name "Net-(U1-VC4)") (class "Default")
      (node (ref "C15") (pin "1") (pinfunction "1_1") (pintype "passive"))
      (node (ref "C16") (pin "2") (pinfunction "2_2") (pintype "passive"))
      (node (ref "R11") (pin "2") (pinfunction "2_2") (pintype "passive"))
      (node (ref "R42") (pin "2") (pinfunction "2_2") (pintype "passive"))
      (node (ref "U1") (pin "37") (pinfunction "VC4_37") (pintype "bidirectional"))
    )
    (net (code "47") (name "Net-(U1-VC5)") (class "Default")
      (node (ref "C16") (pin "1") (pinfunction "1_1") (pintype "passive"))
      (node (ref "D3") (pin "A") (pinfunction "A_A") (pintype "passive"))
      (node (ref "R12") (pin "2") (pinfunction "2_2") (pintype "passive"))
      (node (ref "R44") (pin "2") (pinfunction "2_2") (pintype "passive"))
      (node (ref "U1") (pin "36") (pinfunction "VC5_36") (pintype "bidirectional"))
    )
    (net (code "48") (name "Net-(U1-VC5B)") (class "Default")
      (node (ref "C24") (pin "2") (pinfunction "2_2") (pintype "passive"))
      (node (ref "R13") (pin "2") (pinfunction "2_2") (pintype "passive"))
      (node (ref "U1") (pin "35") (pinfunction "VC5B_35") (pintype "bidirectional"))
    )
    (net (code "49") (name "Net-(U1-VC6)") (class "Default")
      (node (ref "C17") (pin "1") (pinfunction "1_1") (pintype "passive"))
      (node (ref "C18") (pin "2") (pinfunction "2_2") (pintype "passive"))
      (node (ref "R19") (pin "2") (pinfunction "2_2") (pintype "passive"))
      (node (ref "R46") (pin "2") (pinfunction "2_2") (pintype "passive"))
      (node (ref "U1") (pin "34") (pinfunction "VC6_34") (pintype "bidirectional"))
    )
    (net (code "50") (name "Net-(U1-VC7)") (class "Default")
      (node (ref "C18") (pin "1") (pinfunction "1_1") (pintype "passive"))
      (node (ref "C19") (pin "2") (pinfunction "2_2") (pintype "passive"))
      (node (ref "R14") (pin "2") (pinfunction "2_2") (pintype "passive"))
      (node (ref "R48") (pin "2") (pinfunction "2_2") (pintype "passive"))
      (node (ref "U1") (pin "33") (pinfunction "VC7_33") (pintype "bidirectional"))
    )
    (net (code "51") (name "Net-(U1-VC8)") (class "Default")
      (node (ref "C19") (pin "1") (pinfunction "1_1") (pintype "passive"))
      (node (ref "C20") (pin "2") (pinfunction "2_2") (pintype "passive"))
      (node (ref "R15") (pin "2") (pinfunction "2_2") (pintype "passive"))
      (node (ref "R50") (pin "2") (pinfunction "2_2") (pintype "passive"))
      (node (ref "U1") (pin "32") (pinfunction "VC8_32") (pintype "bidirectional"))
    )
    (net (code "52") (name "Net-(U1-VC9)") (class "Default")
      (node (ref "C20") (pin "1") (pinfunction "1_1") (pintype "passive"))
      (node (ref "C21") (pin "2") (pinfunction "2_2") (pintype "passive"))
      (node (ref "R16") (pin "2") (pinfunction "2_2") (pintype "passive"))
      (node (ref "R52") (pin "2") (pinfunction "2_2") (pintype "passive"))
      (node (ref "U1") (pin "31") (pinfunction "VC9_31") (pintype "bidirectional"))
    )
    (net (code "53") (name "Net-(U1-VC10)") (class "Default")
      (node (ref "C21") (pin "1") (pinfunction "1_1") (pintype "passive"))
      (node (ref "D2") (pin "A") (pinfunction "A_A") (pintype "passive"))
      (node (ref "R17") (pin "2") (pinfunction "2_2") (pintype "passive"))
      (node (ref "R54") (pin "2") (pinfunction "2_2") (pintype "passive"))
      (node (ref "U1") (pin "30") (pinfunction "VC10_30") (pintype "bidirectional"))
    )
    (net (code "54") (name "Net-(U1-VC10B)") (class "Default")
      (node (ref "C22") (pin "2") (pinfunction "2_2") (pintype "passive"))
      (node (ref "R20") (pin "2") (pinfunction "2_2") (pintype "passive"))
      (node (ref "U1") (pin "29") (pinfunction "VC10B_29") (pintype "bidirectional"))
    )
    (net (code "55") (name "Net-(U1-VC11)") (class "Default")
      (node (ref "C23") (pin "2") (pinfunction "2_2") (pintype "passive"))
      (node (ref "C25") (pin "1") (pinfunction "1_1") (pintype "passive"))
      (node (ref "R18") (pin "2") (pinfunction "2_2") (pintype "passive"))
      (node (ref "R56") (pin "2") (pinfunction "2_2") (pintype "passive"))
      (node (ref "U1") (pin "28") (pinfunction "VC11_28") (pintype "bidirectional"))
    )
    (net (code "56") (name "Net-(U1-VC12)") (class "Default")
      (node (ref "C23") (pin "1") (pinfunction "1_1") (pintype "passive"))
      (node (ref "C26") (pin "2") (pinfunction "2_2") (pintype "passive"))
      (node (ref "R21") (pin "2") (pinfunction "2_2") (pintype "passive"))
      (node (ref "R58") (pin "2") (pinfunction "2_2") (pintype "passive"))
      (node (ref "U1") (pin "27") (pinfunction "VC12_27") (pintype "bidirectional"))
    )
    (net (code "57") (name "Net-(U1-VC13)") (class "Default")
      (node (ref "C26") (pin "1") (pinfunction "1_1") (pintype "passive"))
      (node (ref "C27") (pin "2") (pinfunction "2_2") (pintype "passive"))
      (node (ref "R22") (pin "2") (pinfunction "2_2") (pintype "passive"))
      (node (ref "R60") (pin "2") (pinfunction "2_2") (pintype "passive"))
      (node (ref "U1") (pin "26") (pinfunction "VC13_26") (pintype "bidirectional"))
    )
    (net (code "58") (name "Net-(U1-VC14)") (class "Default")
      (node (ref "C27") (pin "1") (pinfunction "1_1") (pintype "passive"))
      (node (ref "C28") (pin "2") (pinfunction "2_2") (pintype "passive"))
      (node (ref "R23") (pin "2") (pinfunction "2_2") (pintype "passive"))
      (node (ref "R62") (pin "2") (pinfunction "2_2") (pintype "passive"))
      (node (ref "U1") (pin "25") (pinfunction "VC14_25") (pintype "bidirectional"))
    )
    (net (code "59") (name "Net-(U1-VC15)") (class "Default")
      (node (ref "C28") (pin "1") (pinfunction "1_1") (pintype "passive"))
      (node (ref "D1") (pin "A") (pinfunction "A_A") (pintype "passive"))
      (node (ref "R24") (pin "2") (pinfunction "2_2") (pintype "passive"))
      (node (ref "R64") (pin "2") (pinfunction "2_2") (pintype "passive"))
      (node (ref "U1") (pin "24") (pinfunction "VC15_24") (pintype "bidirectional"))
    )
    (net (code "60") (name "Net-(U2A-D)") (class "Default")
      (node (ref "R29") (pin "1") (pinfunction "1_1") (pintype "passive"))
      (node (ref "U2") (pin "D1") (pinfunction "D_D1") (pintype "passive"))
    )
    (net (code "61") (name "Net-(U2A-G)") (class "Default")
      (node (ref "D8") (pin "A") (pinfunction "A_A") (pintype "passive"))
      (node (ref "R37") (pin "1") (pinfunction "1_1") (pintype "passive"))
      (node (ref "U2") (pin "G1") (pinfunction "G_G1") (pintype "passive"))
    )
    (net (code "62") (name "Net-(U2B-D)") (class "Default")
      (node (ref "R38") (pin "1") (pinfunction "1_1") (pintype "passive"))
      (node (ref "U2") (pin "D2") (pinfunction "D_D2") (pintype "passive"))
    )
    (net (code "63") (name "Net-(U2B-G)") (class "Default")
      (node (ref "D9") (pin "A") (pinfunction "A_A") (pintype "passive"))
      (node (ref "R39") (pin "1") (pinfunction "1_1") (pintype "passive"))
      (node (ref "U2") (pin "G2") (pinfunction "G_G2") (pintype "passive"))
    )
    (net (code "64") (name "Net-(U3A-D)") (class "Default")
      (node (ref "R41") (pin "1") (pinfunction "1_1") (pintype "passive"))
      (node (ref "U3") (pin "D1") (pinfunction "D_D1") (pintype "passive"))
    )
    (net (code "65") (name "Net-(U3A-G)") (class "Default")
      (node (ref "D10") (pin "A") (pinfunction "A_A") (pintype "passive"))
      (node (ref "R40") (pin "1") (pinfunction "1_1") (pintype "passive"))
      (node (ref "U3") (pin "G1") (pinfunction "G_G1") (pintype "passive"))
    )
    (net (code "66") (name "Net-(U3B-D)") (class "Default")
      (node (ref "R43") (pin "1") (pinfunction "1_1") (pintype "passive"))
      (node (ref "U3") (pin "D2") (pinfunction "D_D2") (pintype "passive"))
    )
    (net (code "67") (name "Net-(U3B-G)") (class "Default")
      (node (ref "D11") (pin "A") (pinfunction "A_A") (pintype "passive"))
      (node (ref "R42") (pin "1") (pinfunction "1_1") (pintype "passive"))
      (node (ref "U3") (pin "G2") (pinfunction "G_G2") (pintype "passive"))
    )
    (net (code "68") (name "Net-(U4A-D)") (class "Default")
      (node (ref "R45") (pin "1") (pinfunction "1_1") (pintype "passive"))
      (node (ref "U4") (pin "D1") (pinfunction "D_D1") (pintype "passive"))
    )
    (net (code "69") (name "Net-(U4A-G)") (class "Default")
      (node (ref "D12") (pin "A") (pinfunction "A_A") (pintype "passive"))
      (node (ref "R44") (pin "1") (pinfunction "1_1") (pintype "passive"))
      (node (ref "U4") (pin "G1") (pinfunction "G_G1") (pintype "passive"))
    )
    (net (code "70") (name "Net-(U4B-D)") (class "Default")
      (node (ref "R47") (pin "1") (pinfunction "1_1") (pintype "passive"))
      (node (ref "U4") (pin "D2") (pinfunction "D_D2") (pintype "passive"))
    )
    (net (code "71") (name "Net-(U4B-G)") (class "Default")
      (node (ref "D13") (pin "A") (pinfunction "A_A") (pintype "passive"))
      (node (ref "R46") (pin "1") (pinfunction "1_1") (pintype "passive"))
      (node (ref "U4") (pin "G2") (pinfunction "G_G2") (pintype "passive"))
    )
    (net (code "72") (name "Net-(U5A-D)") (class "Default")
      (node (ref "R49") (pin "1") (pinfunction "1_1") (pintype "passive"))
      (node (ref "U5") (pin "D1") (pinfunction "D_D1") (pintype "passive"))
    )
    (net (code "73") (name "Net-(U5A-G)") (class "Default")
      (node (ref "D14") (pin "A") (pinfunction "A_A") (pintype "passive"))
      (node (ref "R48") (pin "1") (pinfunction "1_1") (pintype "passive"))
      (node (ref "U5") (pin "G1") (pinfunction "G_G1") (pintype "passive"))
    )
    (net (code "74") (name "Net-(U5B-D)") (class "Default")
      (node (ref "R51") (pin "1") (pinfunction "1_1") (pintype "passive"))
      (node (ref "U5") (pin "D2") (pinfunction "D_D2") (pintype "passive"))
    )
    (net (code "75") (name "Net-(U5B-G)") (class "Default")
      (node (ref "D15") (pin "A") (pinfunction "A_A") (pintype "passive"))
      (node (ref "R50") (pin "1") (pinfunction "1_1") (pintype "passive"))
      (node (ref "U5") (pin "G2") (pinfunction "G_G2") (pintype "passive"))
    )
    (net (code "76") (name "Net-(U6A-D)") (class "Default")
      (node (ref "R53") (pin "1") (pinfunction "1_1") (pintype "passive"))
      (node (ref "U6") (pin "D1") (pinfunction "D_D1") (pintype "passive"))
    )
    (net (code "77") (name "Net-(U6A-G)") (class "Default")
      (node (ref "D16") (pin "A") (pinfunction "A_A") (pintype "passive"))
      (node (ref "R52") (pin "1") (pinfunction "1_1") (pintype "passive"))
      (node (ref "U6") (pin "G1") (pinfunction "G_G1") (pintype "passive"))
    )
    (net (code "78") (name "Net-(U6B-D)") (class "Default")
      (node (ref "R55") (pin "1") (pinfunction "1_1") (pintype "passive"))
      (node (ref "U6") (pin "D2") (pinfunction "D_D2") (pintype "passive"))
    )
    (net (code "79") (name "Net-(U6B-G)") (class "Default")
      (node (ref "D17") (pin "A") (pinfunction "A_A") (pintype "passive"))
      (node (ref "R54") (pin "1") (pinfunction "1_1") (pintype "passive"))
      (node (ref "U6") (pin "G2") (pinfunction "G_G2") (pintype "passive"))
    )
    (net (code "80") (name "Net-(U7A-D)") (class "Default")
      (node (ref "R57") (pin "1") (pinfunction "1_1") (pintype "passive"))
      (node (ref "U7") (pin "D1") (pinfunction "D_D1") (pintype "passive"))
    )
    (net (code "81") (name "Net-(U7A-G)") (class "Default")
      (node (ref "D18") (pin "A") (pinfunction "A_A") (pintype "passive"))
      (node (ref "R56") (pin "1") (pinfunction "1_1") (pintype "passive"))
      (node (ref "U7") (pin "G1") (pinfunction "G_G1") (pintype "passive"))
    )
    (net (code "82") (name "Net-(U7B-D)") (class "Default")
      (node (ref "R59") (pin "1") (pinfunction "1_1") (pintype "passive"))
      (node (ref "U7") (pin "D2") (pinfunction "D_D2") (pintype "passive"))
    )
    (net (code "83") (name "Net-(U7B-G)") (class "Default")
      (node (ref "D19") (pin "A") (pinfunction "A_A") (pintype "passive"))
      (node (ref "R58") (pin "1") (pinfunction "1_1") (pintype "passive"))
      (node (ref "U7") (pin "G2") (pinfunction "G_G2") (pintype "passive"))
    )
    (net (code "84") (name "Net-(U8A-D)") (class "Default")
      (node (ref "R61") (pin "1") (pinfunction "1_1") (pintype "passive"))
      (node (ref "U8") (pin "D1") (pinfunction "D_D1") (pintype "passive"))
    )
    (net (code "85") (name "Net-(U8A-G)") (class "Default")
      (node (ref "D20") (pin "A") (pinfunction "A_A") (pintype "passive"))
      (node (ref "R60") (pin "1") (pinfunction "1_1") (pintype "passive"))
      (node (ref "U8") (pin "G1") (pinfunction "G_G1") (pintype "passive"))
    )
    (net (code "86") (name "Net-(U8B-D)") (class "Default")
      (node (ref "R63") (pin "1") (pinfunction "1_1") (pintype "passive"))
      (node (ref "U8") (pin "D2") (pinfunction "D_D2") (pintype "passive"))
    )
    (net (code "87") (name "Net-(U8B-G)") (class "Default")
      (node (ref "D21") (pin "A") (pinfunction "A_A") (pintype "passive"))
      (node (ref "R62") (pin "1") (pinfunction "1_1") (pintype "passive"))
      (node (ref "U8") (pin "G2") (pinfunction "G_G2") (pintype "passive"))
    )
    (net (code "88") (name "Net-(U9A-D)") (class "Default")
      (node (ref "R65") (pin "1") (pinfunction "1_1") (pintype "passive"))
      (node (ref "U9") (pin "D1") (pinfunction "D_D1") (pintype "passive"))
    )
    (net (code "89") (name "Net-(U9A-G)") (class "Default")
      (node (ref "D22") (pin "A") (pinfunction "A_A") (pintype "passive"))
      (node (ref "R64") (pin "1") (pinfunction "1_1") (pintype "passive"))
      (node (ref "U9") (pin "G1") (pinfunction "G_G1") (pintype "passive"))
    )
    (net (code "90") (name "PACK+") (class "Default")
      (node (ref "C38") (pin "2") (pinfunction "2_2") (pintype "passive"))
      (node (ref "D22") (pin "C") (pinfunction "C_C") (pintype "passive"))
      (node (ref "D6") (pin "C") (pinfunction "C_C") (pintype "passive"))
      (node (ref "D7") (pin "C") (pinfunction "C_C") (pintype "passive"))
      (node (ref "JP5") (pin "4") (pinfunction "4_4") (pintype "passive"))
      (node (ref "Q1") (pin "3") (pinfunction "D_3") (pintype "passive"))
      (node (ref "R24") (pin "1") (pinfunction "1_1") (pintype "passive"))
      (node (ref "R3") (pin "1") (pinfunction "1_1") (pintype "passive"))
      (node (ref "U9") (pin "S1") (pinfunction "S_S1") (pintype "passive"))
    )
    (net (code "91") (name "REGOUT") (class "Default")
      (node (ref "C1") (pin "1") (pinfunction "1_1") (pintype "passive"))
      (node (ref "JP10") (pin "2") (pinfunction "2_2") (pintype "passive"))
      (node (ref "SJ1") (pin "2") (pinfunction "2_2") (pintype "passive"))
      (node (ref "SJ5") (pin "2") (pinfunction "2_2") (pintype "passive"))
      (node (ref "U1") (pin "8") (pinfunction "REGOUT_8") (pintype "bidirectional"))
    )
    (net (code "92") (name "SCL") (class "Default")
      (node (ref "JP10") (pin "4") (pinfunction "4_4") (pintype "passive"))
      (node (ref "R1") (pin "1") (pinfunction "1_1") (pintype "passive"))
      (node (ref "U1") (pin "5") (pinfunction "SCL_5") (pintype "bidirectional"))
    )
    (net (code "93") (name "SDA") (class "Default")
      (node (ref "JP10") (pin "3") (pinfunction "3_3") (pintype "passive"))
      (node (ref "R2") (pin "1") (pinfunction "1_1") (pintype "passive"))
      (node (ref "U1") (pin "4") (pinfunction "SDA_4") (pintype "bidirectional"))
    )
    (net (code "94") (name "SRN") (class "Default")
      (node (ref "C31") (pin "2") (pinfunction "2_2") (pintype "passive"))
      (node (ref "U1") (pin "43") (pinfunction "SRN_43") (pintype "bidirectional"))
    )
    (net (code "95") (name "SRP") (class "Default")
      (node (ref "C29") (pin "1") (pinfunction "1_1") (pintype "passive"))
      (node (ref "U1") (pin "42") (pinfunction "SRP_42") (pintype "bidirectional"))
    )
    (net (code "96") (name "TS1") (class "Default")
      (node (ref "C2") (pin "1") (pinfunction "1_1") (pintype "passive"))
      (node (ref "JP8") (pin "2") (pinfunction "2_2") (pintype "passive"))
      (node (ref "R26") (pin "2") (pinfunction "2_2") (pintype "passive"))
      (node (ref "SJ2") (pin "2") (pinfunction "2_2") (pintype "passive"))
      (node (ref "U1") (pin "6") (pinfunction "TS1_6") (pintype "bidirectional"))
    )
    (net (code "97") (name "TS2") (class "Default")
      (node (ref "C9") (pin "1") (pinfunction "1_1") (pintype "passive"))
      (node (ref "JP6") (pin "2") (pinfunction "2_2") (pintype "passive"))
      (node (ref "SJ3") (pin "2") (pinfunction "2_2") (pintype "passive"))
      (node (ref "U1") (pin "13") (pinfunction "TS2_13") (pintype "bidirectional"))
    )
    (net (code "98") (name "TS3") (class "Default")
      (node (ref "C10") (pin "1") (pinfunction "1_1") (pintype "passive"))
      (node (ref "JP9") (pin "2") (pinfunction "2_2") (pintype "passive"))
      (node (ref "SJ4") (pin "2") (pinfunction "2_2") (pintype "passive"))
      (node (ref "U1") (pin "18") (pinfunction "TS3_18") (pintype "bidirectional"))
    )
    (net (code "99") (name "VC5X") (class "Default")
      (node (ref "C17") (pin "2") (pinfunction "2_2") (pintype "passive"))
      (node (ref "C24") (pin "1") (pinfunction "1_1") (pintype "passive"))
      (node (ref "C33") (pin "2") (pinfunction "2_2") (pintype "passive"))
      (node (ref "C34") (pin "1") (pinfunction "1_1") (pintype "passive"))
      (node (ref "C4") (pin "2") (pinfunction "2_2") (pintype "passive"))
      (node (ref "C9") (pin "2") (pinfunction "2_2") (pintype "passive"))
      (node (ref "D3") (pin "C") (pinfunction "C_C") (pintype "passive"))
      (node (ref "Q1") (pin "1") (pinfunction "G_1") (pintype "passive"))
      (node (ref "R31") (pin "1") (pinfunction "1_1") (pintype "passive"))
      (node (ref "R33") (pin "1") (pinfunction "1_1") (pintype "passive"))
      (node (ref "U1") (pin "10") (pinfunction "VC5X_10") (pintype "bidirectional"))
    )
    (net (code "100") (name "VC10X") (class "Default")
      (node (ref "C10") (pin "2") (pinfunction "2_2") (pintype "passive"))
      (node (ref "C22") (pin "1") (pinfunction "1_1") (pintype "passive"))
      (node (ref "C25") (pin "2") (pinfunction "2_2") (pintype "passive"))
      (node (ref "C32") (pin "2") (pinfunction "2_2") (pintype "passive"))
      (node (ref "C33") (pin "1") (pinfunction "1_1") (pintype "passive"))
      (node (ref "C6") (pin "2") (pinfunction "2_2") (pintype "passive"))
      (node (ref "D2") (pin "C") (pinfunction "C_C") (pintype "passive"))
      (node (ref "R30") (pin "1") (pinfunction "1_1") (pintype "passive"))
      (node (ref "R34") (pin "1") (pinfunction "1_1") (pintype "passive"))
      (node (ref "U1") (pin "15") (pinfunction "VC10X_15") (pintype "bidirectional"))
    )
    (net (code "101") (name "unconnected-(U1-NC-Pad21)") (class "Default")
      (node (ref "U1") (pin "21") (pinfunction "NC_21") (pintype "bidirectional"))
    )
    (net (code "102") (name "unconnected-(U1-NC-Pad22)") (class "Default")
      (node (ref "U1") (pin "22") (pinfunction "NC_22") (pintype "bidirectional"))
    )
    (net (code "103") (name "unconnected-(U1-NC-Pad23)") (class "Default")
      (node (ref "U1") (pin "23") (pinfunction "NC_23") (pintype "bidirectional"))
    )
    (net (code "104") (name "unconnected-(U9B-D-PadD2)") (class "Default")
      (node (ref "U9") (pin "D2") (pinfunction "D_D2") (pintype "passive"))
    )
    (net (code "105") (name "unconnected-(U9B-G-PadG2)") (class "Default")
      (node (ref "U9") (pin "G2") (pinfunction "G_G2") (pintype "passive"))
    )
    (net (code "106") (name "unconnected-(U9B-S-PadS2)") (class "Default")
      (node (ref "U9") (pin "S2") (pinfunction "S_S2") (pintype "passive"))
    )
  )
)
